# 1_P1_schdoc.net
KiCad netlist of a schematic drawn in Altium Designer
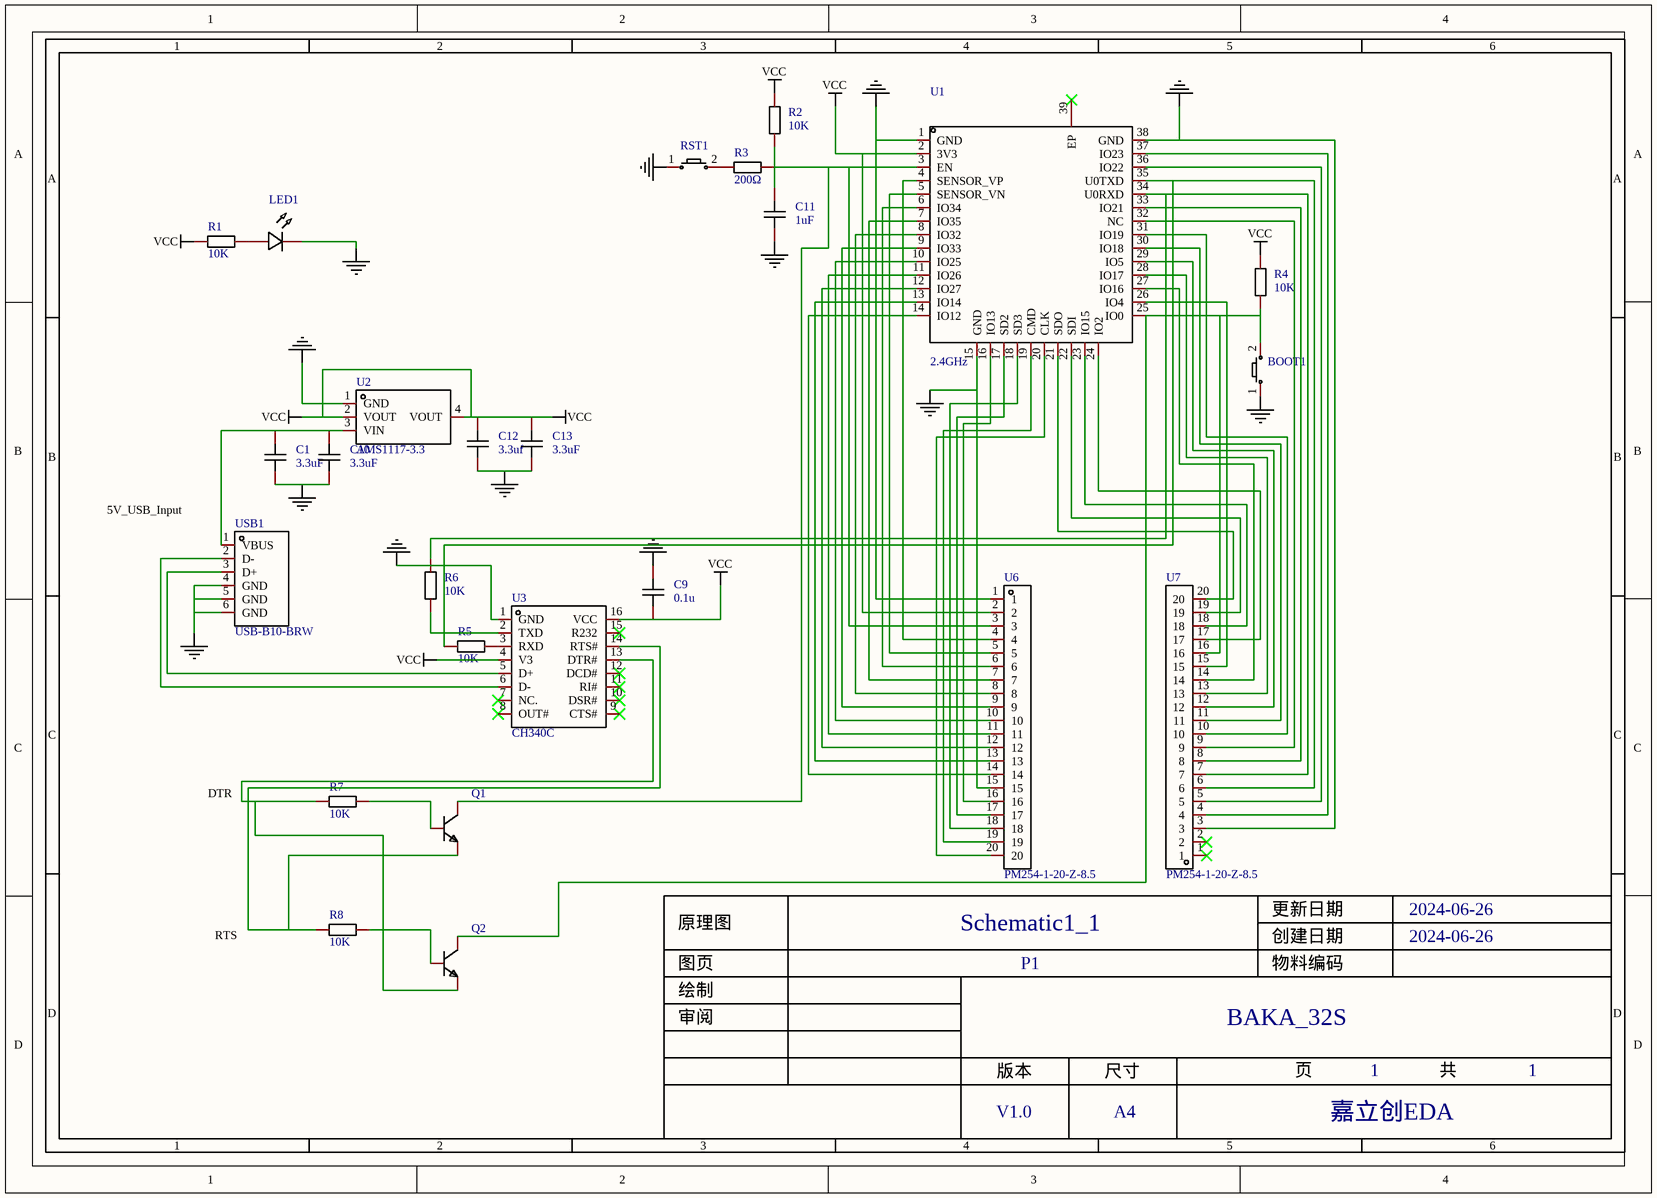
[diagram p0: 1_P1.schdoc.schdoc]

(export (version "E")
  (design (tool "Eeschema 10.0.6"))
  (components
    (comp (ref "BOOT1")
      (value "Key_SMD_3x4x2")
      (libsource (lib "altium-import") (part "root_1_Key_SMD_3x4x2_"))
    )
    (comp (ref "C1")
      (value "3.3uF")
      (fields (field (name "NAME") "3.3uF"))
      (libsource (lib "altium-import") (part "root_1_CAP_0603_"))
    )
    (comp (ref "C9")
      (value "0.1u")
      (fields (field (name "NAME") "0.1u"))
      (libsource (lib "altium-import") (part "root_1_CAP_0603_"))
    )
    (comp (ref "C10")
      (value "3.3uF")
      (fields (field (name "NAME") "3.3uF"))
      (libsource (lib "altium-import") (part "root_1_CAP_0603_"))
    )
    (comp (ref "C11")
      (value "1uF")
      (fields (field (name "NAME") "1uF"))
      (libsource (lib "altium-import") (part "root_1_CAP_0603_"))
    )
    (comp (ref "C12")
      (value "3.3uf")
      (fields (field (name "NAME") "3.3uf"))
      (libsource (lib "altium-import") (part "root_1_CAP_0603_"))
    )
    (comp (ref "C13")
      (value "3.3uF")
      (fields (field (name "NAME") "3.3uF"))
      (libsource (lib "altium-import") (part "root_1_CAP_0603_"))
    )
    (comp (ref "LED1") (value "LED_0603-R") (libsource (lib "altium-import") (part "root_0_LED_0603-R_")))
    (comp (ref "Q1") (value "S8050_SOT_NPN") (libsource (lib "altium-import") (part "root_0_S8050_SOT_NPN_")))
    (comp (ref "Q2") (value "S8050_SOT_NPN") (libsource (lib "altium-import") (part "root_0_S8050_SOT_NPN_")))
    (comp (ref "R1")
      (value "10K")
      (fields (field (name "NAME") "10K"))
      (libsource (lib "altium-import") (part "root_0_Res_0603_"))
    )
    (comp (ref "R2")
      (value "10K")
      (fields (field (name "NAME") "10K"))
      (libsource (lib "altium-import") (part "root_1_Res_0603_"))
    )
    (comp (ref "R3")
      (value "200Ω")
      (fields (field (name "NAME") "200Ω"))
      (libsource (lib "altium-import") (part "root_0_Res_0603_"))
    )
    (comp (ref "R4")
      (value "10K")
      (fields (field (name "NAME") "10K"))
      (libsource (lib "altium-import") (part "root_1_Res_0603_"))
    )
    (comp (ref "R5")
      (value "10K")
      (fields (field (name "NAME") "10K"))
      (libsource (lib "altium-import") (part "root_0_Res_0603_"))
    )
    (comp (ref "R6")
      (value "10K")
      (fields (field (name "NAME") "10K"))
      (libsource (lib "altium-import") (part "root_1_Res_0603_"))
    )
    (comp (ref "R7")
      (value "10K")
      (fields (field (name "NAME") "10K"))
      (libsource (lib "altium-import") (part "root_0_Res_0603_"))
    )
    (comp (ref "R8")
      (value "10K")
      (fields (field (name "NAME") "10K"))
      (libsource (lib "altium-import") (part "root_0_Res_0603_"))
    )
    (comp (ref "RST1")
      (value "Key_SMD_3x4x2")
      (libsource (lib "altium-import") (part "root_0_Key_SMD_3x4x2_"))
    )
    (comp (ref "U1")
      (value "2.4GHz")
      (description "核心处理器:ESP32芯片;频率:2.4GHz;天线形式:IPEX接口;发射功率:17dBm;接收灵敏度:-90dBm;")
      (fields
        (field (name "NAME") "2.4GHz")
        (field (name "MANUFACTURER") "Ai-Thinker(安信可)")
        (field (name "MANUFACTURER PART") "ESP32-S")
      )
      (libsource (lib "altium-import") (part "root_0_ESP32-S_"))
    )
    (comp (ref "U2")
      (value "AMS1117-3.3")
      (description "输出类型:固定;最大输入电压:-;输出电压:3.3V;最大输出电流:1A;电源纹波抑制比(PSRR):72dB@(120Hz);输出极性:正极;")
      (fields (field (name "NAME") "AMS1117-3.3") (field (name "MANUFACTURER") "AMS"))
      (libsource (lib "altium-import") (part "root_0_AMS1117-3.3_C6186_"))
    )
    (comp (ref "U3")
      (value "CH340C")
      (description "应用功能:收发器;接口协议:USB 2.0;数据速率:2Mbps;")
      (fields (field (name "NAME") "CH340C") (field (name "MANUFACTURER") "WCH(南京沁恒)"))
      (libsource (lib "altium-import") (part "root_0_CH340C_"))
    )
    (comp (ref "U6")
      (value "PM254-1-20-Z-8.5")
      (fields (field (name "NAME") "PM254-1-20-Z-8.5") (field (name "MANUFACTURER") "HCTL(华灿天禄)"))
      (libsource (lib "altium-import") (part "root_0_PM254-1-20-Z-8.5_"))
    )
    (comp (ref "U7")
      (value "PM254-1-20-Z-8.5")
      (fields (field (name "NAME") "PM254-1-20-Z-8.5") (field (name "MANUFACTURER") "HCTL(华灿天禄)"))
      (libsource (lib "altium-import") (part "root_2_PM254-1-20-Z-8.5_"))
    )
    (comp (ref "USB1")
      (value "USB-B10-BRW")
      (fields (field (name "NAME") "USB-B10-BRW") (field (name "MANUFACTURER") "XUNPU(讯普)"))
      (libsource (lib "altium-import") (part "root_0_USB-B10-BRW_"))
    )
  )
  (nets
    (net (code "1") (name "GND") (class "Default")
      (node (ref "BOOT1") (pin "1") (pinfunction "1_1") (pintype "passive"))
      (node (ref "C1") (pin "1") (pinfunction "1_1") (pintype "passive"))
      (node (ref "C10") (pin "1") (pinfunction "1_1") (pintype "passive"))
      (node (ref "C11") (pin "1") (pinfunction "1_1") (pintype "passive"))
      (node (ref "C12") (pin "1") (pinfunction "1_1") (pintype "passive"))
      (node (ref "C13") (pin "1") (pinfunction "1_1") (pintype "passive"))
      (node (ref "C9") (pin "2") (pinfunction "2_2") (pintype "passive"))
      (node (ref "LED1") (pin "1") (pinfunction "C_1") (pintype "passive"))
      (node (ref "RST1") (pin "1") (pinfunction "1_1") (pintype "passive"))
      (node (ref "U1") (pin "1") (pinfunction "GND_1") (pintype "passive"))
      (node (ref "U1") (pin "15") (pinfunction "GND_15") (pintype "passive"))
      (node (ref "U1") (pin "38") (pinfunction "GND_38") (pintype "passive"))
      (node (ref "U2") (pin "1") (pinfunction "GND_1") (pintype "passive"))
      (node (ref "U3") (pin "1") (pinfunction "GND_1") (pintype "passive"))
      (node (ref "U6") (pin "1") (pinfunction "1_1") (pintype "passive"))
      (node (ref "U6") (pin "15") (pinfunction "15_15") (pintype "passive"))
      (node (ref "U7") (pin "3") (pinfunction "3_3") (pintype "passive"))
      (node (ref "USB1") (pin "4") (pinfunction "GND_4") (pintype "passive"))
      (node (ref "USB1") (pin "5") (pinfunction "GND_5") (pintype "passive"))
      (node (ref "USB1") (pin "6") (pinfunction "GND_6") (pintype "passive"))
    )
    (net (code "2") (name "Net-(LED1-A)") (class "Default")
      (node (ref "LED1") (pin "2") (pinfunction "A_2") (pintype "passive"))
      (node (ref "R1") (pin "2") (pinfunction "2_2") (pintype "passive"))
    )
    (net (code "3") (name "Net-(Q1-Pad1)") (class "Default")
      (node (ref "Q1") (pin "1") (pinfunction "1_1") (pintype "passive"))
      (node (ref "R7") (pin "2") (pinfunction "2_2") (pintype "passive"))
    )
    (net (code "4") (name "Net-(Q2-Pad1)") (class "Default")
      (node (ref "Q2") (pin "1") (pinfunction "1_1") (pintype "passive"))
      (node (ref "R8") (pin "2") (pinfunction "2_2") (pintype "passive"))
    )
    (net (code "5") (name "Net-(R3-Pad1)") (class "Default")
      (node (ref "R3") (pin "1") (pinfunction "1_1") (pintype "passive"))
      (node (ref "RST1") (pin "2") (pinfunction "2_2") (pintype "passive"))
    )
    (net (code "6") (name "Net-(U1-CLK)") (class "Default")
      (node (ref "U1") (pin "20") (pinfunction "CLK_20") (pintype "passive"))
      (node (ref "U6") (pin "20") (pinfunction "20_20") (pintype "passive"))
    )
    (net (code "7") (name "Net-(U1-CMD)") (class "Default")
      (node (ref "U1") (pin "19") (pinfunction "CMD_19") (pintype "passive"))
      (node (ref "U6") (pin "19") (pinfunction "19_19") (pintype "passive"))
    )
    (net (code "8") (name "Net-(U1-EN)") (class "Default")
      (node (ref "C11") (pin "2") (pinfunction "2_2") (pintype "passive"))
      (node (ref "Q1") (pin "3") (pinfunction "3_3") (pintype "passive"))
      (node (ref "R2") (pin "1") (pinfunction "1_1") (pintype "passive"))
      (node (ref "R3") (pin "2") (pinfunction "2_2") (pintype "passive"))
      (node (ref "U1") (pin "3") (pinfunction "EN_3") (pintype "passive"))
      (node (ref "U6") (pin "3") (pinfunction "3_3") (pintype "passive"))
    )
    (net (code "9") (name "Net-(U1-IO0)") (class "Default")
      (node (ref "BOOT1") (pin "2") (pinfunction "2_2") (pintype "passive"))
      (node (ref "Q2") (pin "3") (pinfunction "3_3") (pintype "passive"))
      (node (ref "R4") (pin "1") (pinfunction "1_1") (pintype "passive"))
      (node (ref "U1") (pin "25") (pinfunction "IO0_25") (pintype "passive"))
      (node (ref "U7") (pin "16") (pinfunction "16_16") (pintype "passive"))
    )
    (net (code "10") (name "Net-(U1-IO2)") (class "Default")
      (node (ref "U1") (pin "24") (pinfunction "IO2_24") (pintype "passive"))
      (node (ref "U7") (pin "17") (pinfunction "17_17") (pintype "passive"))
    )
    (net (code "11") (name "Net-(U1-IO4)") (class "Default")
      (node (ref "U1") (pin "26") (pinfunction "IO4_26") (pintype "passive"))
      (node (ref "U7") (pin "15") (pinfunction "15_15") (pintype "passive"))
    )
    (net (code "12") (name "Net-(U1-IO5)") (class "Default")
      (node (ref "U1") (pin "29") (pinfunction "IO5_29") (pintype "passive"))
      (node (ref "U7") (pin "12") (pinfunction "12_12") (pintype "passive"))
    )
    (net (code "13") (name "Net-(U1-IO12)") (class "Default")
      (node (ref "U1") (pin "14") (pinfunction "IO12_14") (pintype "passive"))
      (node (ref "U6") (pin "14") (pinfunction "14_14") (pintype "passive"))
    )
    (net (code "14") (name "Net-(U1-IO13)") (class "Default")
      (node (ref "U1") (pin "16") (pinfunction "IO13_16") (pintype "passive"))
      (node (ref "U6") (pin "16") (pinfunction "16_16") (pintype "passive"))
    )
    (net (code "15") (name "Net-(U1-IO14)") (class "Default")
      (node (ref "U1") (pin "13") (pinfunction "IO14_13") (pintype "passive"))
      (node (ref "U6") (pin "13") (pinfunction "13_13") (pintype "passive"))
    )
    (net (code "16") (name "Net-(U1-IO15)") (class "Default")
      (node (ref "U1") (pin "23") (pinfunction "IO15_23") (pintype "passive"))
      (node (ref "U7") (pin "18") (pinfunction "18_18") (pintype "passive"))
    )
    (net (code "17") (name "Net-(U1-IO16)") (class "Default")
      (node (ref "U1") (pin "27") (pinfunction "IO16_27") (pintype "passive"))
      (node (ref "U7") (pin "14") (pinfunction "14_14") (pintype "passive"))
    )
    (net (code "18") (name "Net-(U1-IO17)") (class "Default")
      (node (ref "U1") (pin "28") (pinfunction "IO17_28") (pintype "passive"))
      (node (ref "U7") (pin "13") (pinfunction "13_13") (pintype "passive"))
    )
    (net (code "19") (name "Net-(U1-IO18)") (class "Default")
      (node (ref "U1") (pin "30") (pinfunction "IO18_30") (pintype "passive"))
      (node (ref "U7") (pin "11") (pinfunction "11_11") (pintype "passive"))
    )
    (net (code "20") (name "Net-(U1-IO19)") (class "Default")
      (node (ref "U1") (pin "31") (pinfunction "IO19_31") (pintype "passive"))
      (node (ref "U7") (pin "10") (pinfunction "10_10") (pintype "passive"))
    )
    (net (code "21") (name "Net-(U1-IO21)") (class "Default")
      (node (ref "U1") (pin "33") (pinfunction "IO21_33") (pintype "passive"))
      (node (ref "U7") (pin "8") (pinfunction "8_8") (pintype "passive"))
    )
    (net (code "22") (name "Net-(U1-IO22)") (class "Default")
      (node (ref "U1") (pin "36") (pinfunction "IO22_36") (pintype "passive"))
      (node (ref "U7") (pin "5") (pinfunction "5_5") (pintype "passive"))
    )
    (net (code "23") (name "Net-(U1-IO23)") (class "Default")
      (node (ref "U1") (pin "37") (pinfunction "IO23_37") (pintype "passive"))
      (node (ref "U7") (pin "4") (pinfunction "4_4") (pintype "passive"))
    )
    (net (code "24") (name "Net-(U1-IO25)") (class "Default")
      (node (ref "U1") (pin "10") (pinfunction "IO25_10") (pintype "passive"))
      (node (ref "U6") (pin "10") (pinfunction "10_10") (pintype "passive"))
    )
    (net (code "25") (name "Net-(U1-IO26)") (class "Default")
      (node (ref "U1") (pin "11") (pinfunction "IO26_11") (pintype "passive"))
      (node (ref "U6") (pin "11") (pinfunction "11_11") (pintype "passive"))
    )
    (net (code "26") (name "Net-(U1-IO27)") (class "Default")
      (node (ref "U1") (pin "12") (pinfunction "IO27_12") (pintype "passive"))
      (node (ref "U6") (pin "12") (pinfunction "12_12") (pintype "passive"))
    )
    (net (code "27") (name "Net-(U1-IO32)") (class "Default")
      (node (ref "U1") (pin "8") (pinfunction "IO32_8") (pintype "passive"))
      (node (ref "U6") (pin "8") (pinfunction "8_8") (pintype "passive"))
    )
    (net (code "28") (name "Net-(U1-IO33)") (class "Default")
      (node (ref "U1") (pin "9") (pinfunction "IO33_9") (pintype "passive"))
      (node (ref "U6") (pin "9") (pinfunction "9_9") (pintype "passive"))
    )
    (net (code "29") (name "Net-(U1-IO34)") (class "Default")
      (node (ref "U1") (pin "6") (pinfunction "IO34_6") (pintype "passive"))
      (node (ref "U6") (pin "6") (pinfunction "6_6") (pintype "passive"))
    )
    (net (code "30") (name "Net-(U1-IO35)") (class "Default")
      (node (ref "U1") (pin "7") (pinfunction "IO35_7") (pintype "passive"))
      (node (ref "U6") (pin "7") (pinfunction "7_7") (pintype "passive"))
    )
    (net (code "31") (name "Net-(U1-NC)") (class "Default")
      (node (ref "U1") (pin "32") (pinfunction "NC_32") (pintype "passive"))
      (node (ref "U7") (pin "9") (pinfunction "9_9") (pintype "passive"))
    )
    (net (code "32") (name "Net-(U1-SD2)") (class "Default")
      (node (ref "U1") (pin "17") (pinfunction "SD2_17") (pintype "passive"))
      (node (ref "U6") (pin "17") (pinfunction "17_17") (pintype "passive"))
    )
    (net (code "33") (name "Net-(U1-SD3)") (class "Default")
      (node (ref "U1") (pin "18") (pinfunction "SD3_18") (pintype "passive"))
      (node (ref "U6") (pin "18") (pinfunction "18_18") (pintype "passive"))
    )
    (net (code "34") (name "Net-(U1-SDI)") (class "Default")
      (node (ref "U1") (pin "22") (pinfunction "SDI_22") (pintype "passive"))
      (node (ref "U7") (pin "19") (pinfunction "19_19") (pintype "passive"))
    )
    (net (code "35") (name "Net-(U1-SDO)") (class "Default")
      (node (ref "U1") (pin "21") (pinfunction "SDO_21") (pintype "passive"))
      (node (ref "U7") (pin "20") (pinfunction "20_20") (pintype "passive"))
    )
    (net (code "36") (name "Net-(U1-SENSOR_VN)") (class "Default")
      (node (ref "U1") (pin "5") (pinfunction "SENSOR_VN_5") (pintype "passive"))
      (node (ref "U6") (pin "5") (pinfunction "5_5") (pintype "passive"))
    )
    (net (code "37") (name "Net-(U1-SENSOR_VP)") (class "Default")
      (node (ref "U1") (pin "4") (pinfunction "SENSOR_VP_4") (pintype "passive"))
      (node (ref "U6") (pin "4") (pinfunction "4_4") (pintype "passive"))
    )
    (net (code "38") (name "Net-(U1-U0RXD)") (class "Default")
      (node (ref "R6") (pin "2") (pinfunction "2_2") (pintype "passive"))
      (node (ref "U1") (pin "34") (pinfunction "U0RXD_34") (pintype "passive"))
      (node (ref "U7") (pin "7") (pinfunction "7_7") (pintype "passive"))
    )
    (net (code "39") (name "Net-(U1-U0TXD)") (class "Default")
      (node (ref "R5") (pin "1") (pinfunction "1_1") (pintype "passive"))
      (node (ref "U1") (pin "35") (pinfunction "U0TXD_35") (pintype "passive"))
      (node (ref "U7") (pin "6") (pinfunction "6_6") (pintype "passive"))
    )
    (net (code "40") (name "Net-(U2-VIN)") (class "Default")
      (node (ref "C1") (pin "2") (pinfunction "2_2") (pintype "passive"))
      (node (ref "C10") (pin "2") (pinfunction "2_2") (pintype "passive"))
      (node (ref "U2") (pin "3") (pinfunction "VIN_3") (pintype "passive"))
      (node (ref "USB1") (pin "1") (pinfunction "VBUS_1") (pintype "passive"))
    )
    (net (code "41") (name "Net-(U3-D+)") (class "Default")
      (node (ref "U3") (pin "5") (pinfunction "D+_5") (pintype "passive"))
      (node (ref "USB1") (pin "3") (pinfunction "D+_3") (pintype "passive"))
    )
    (net (code "42") (name "Net-(U3-D-)") (class "Default")
      (node (ref "U3") (pin "6") (pinfunction "D-_6") (pintype "passive"))
      (node (ref "USB1") (pin "2") (pinfunction "D-_2") (pintype "passive"))
    )
    (net (code "43") (name "Net-(U3-DTR#)") (class "Default")
      (node (ref "Q2") (pin "2") (pinfunction "2_2") (pintype "passive"))
      (node (ref "R7") (pin "1") (pinfunction "1_1") (pintype "passive"))
      (node (ref "U3") (pin "13") (pinfunction "DTR#_13") (pintype "passive"))
    )
    (net (code "44") (name "Net-(U3-RTS#)") (class "Default")
      (node (ref "Q1") (pin "2") (pinfunction "2_2") (pintype "passive"))
      (node (ref "R8") (pin "1") (pinfunction "1_1") (pintype "passive"))
      (node (ref "U3") (pin "14") (pinfunction "RTS#_14") (pintype "passive"))
    )
    (net (code "45") (name "Net-(U3-RXD)") (class "Default")
      (node (ref "R5") (pin "2") (pinfunction "2_2") (pintype "passive"))
      (node (ref "U3") (pin "3") (pinfunction "RXD_3") (pintype "passive"))
    )
    (net (code "46") (name "Net-(U3-TXD)") (class "Default")
      (node (ref "R6") (pin "1") (pinfunction "1_1") (pintype "passive"))
      (node (ref "U3") (pin "2") (pinfunction "TXD_2") (pintype "passive"))
    )
    (net (code "47") (name "VCC") (class "Default")
      (node (ref "C12") (pin "2") (pinfunction "2_2") (pintype "passive"))
      (node (ref "C13") (pin "2") (pinfunction "2_2") (pintype "passive"))
      (node (ref "C9") (pin "1") (pinfunction "1_1") (pintype "passive"))
      (node (ref "R1") (pin "1") (pinfunction "1_1") (pintype "passive"))
      (node (ref "R2") (pin "2") (pinfunction "2_2") (pintype "passive"))
      (node (ref "R4") (pin "2") (pinfunction "2_2") (pintype "passive"))
      (node (ref "U1") (pin "2") (pinfunction "3V3_2") (pintype "passive"))
      (node (ref "U2") (pin "2") (pinfunction "VOUT_2") (pintype "passive"))
      (node (ref "U2") (pin "4") (pinfunction "VOUT_4") (pintype "passive"))
      (node (ref "U3") (pin "16") (pinfunction "VCC_16") (pintype "passive"))
      (node (ref "U3") (pin "4") (pinfunction "V3_4") (pintype "passive"))
      (node (ref "U6") (pin "2") (pinfunction "2_2") (pintype "passive"))
    )
    (net (code "48") (name "unconnected-(U1-EP-Pad39)") (class "Default")
      (node (ref "U1") (pin "39") (pinfunction "EP_39") (pintype "passive+no_connect"))
    )
    (net (code "49") (name "unconnected-(U3-CTS#-Pad9)") (class "Default")
      (node (ref "U3") (pin "9") (pinfunction "CTS#_9") (pintype "passive+no_connect"))
    )
    (net (code "50") (name "unconnected-(U3-DCD#-Pad12)") (class "Default")
      (node (ref "U3") (pin "12") (pinfunction "DCD#_12") (pintype "passive+no_connect"))
    )
    (net (code "51") (name "unconnected-(U3-DSR#-Pad10)") (class "Default")
      (node (ref "U3") (pin "10") (pinfunction "DSR#_10") (pintype "passive+no_connect"))
    )
    (net (code "52") (name "unconnected-(U3-NC.-Pad7)") (class "Default")
      (node (ref "U3") (pin "7") (pinfunction "NC._7") (pintype "passive+no_connect"))
    )
    (net (code "53") (name "unconnected-(U3-OUT#-Pad8)") (class "Default")
      (node (ref "U3") (pin "8") (pinfunction "OUT#_8") (pintype "passive+no_connect"))
    )
    (net (code "54") (name "unconnected-(U3-R232-Pad15)") (class "Default")
      (node (ref "U3") (pin "15") (pinfunction "R232_15") (pintype "passive+no_connect"))
    )
    (net (code "55") (name "unconnected-(U3-RI#-Pad11)") (class "Default")
      (node (ref "U3") (pin "11") (pinfunction "RI#_11") (pintype "passive+no_connect"))
    )
    (net (code "56") (name "unconnected-(U7-Pad1)") (class "Default")
      (node (ref "U7") (pin "1") (pinfunction "1_1") (pintype "passive+no_connect"))
    )
    (net (code "57") (name "unconnected-(U7-Pad2)") (class "Default")
      (node (ref "U7") (pin "2") (pinfunction "2_2") (pintype "passive+no_connect"))
    )
  )
)
